# EASYEADA_SCH_WaterLevelAtmega328_2022-11.net
KiCad netlist of a schematic drawn in EasyEDA
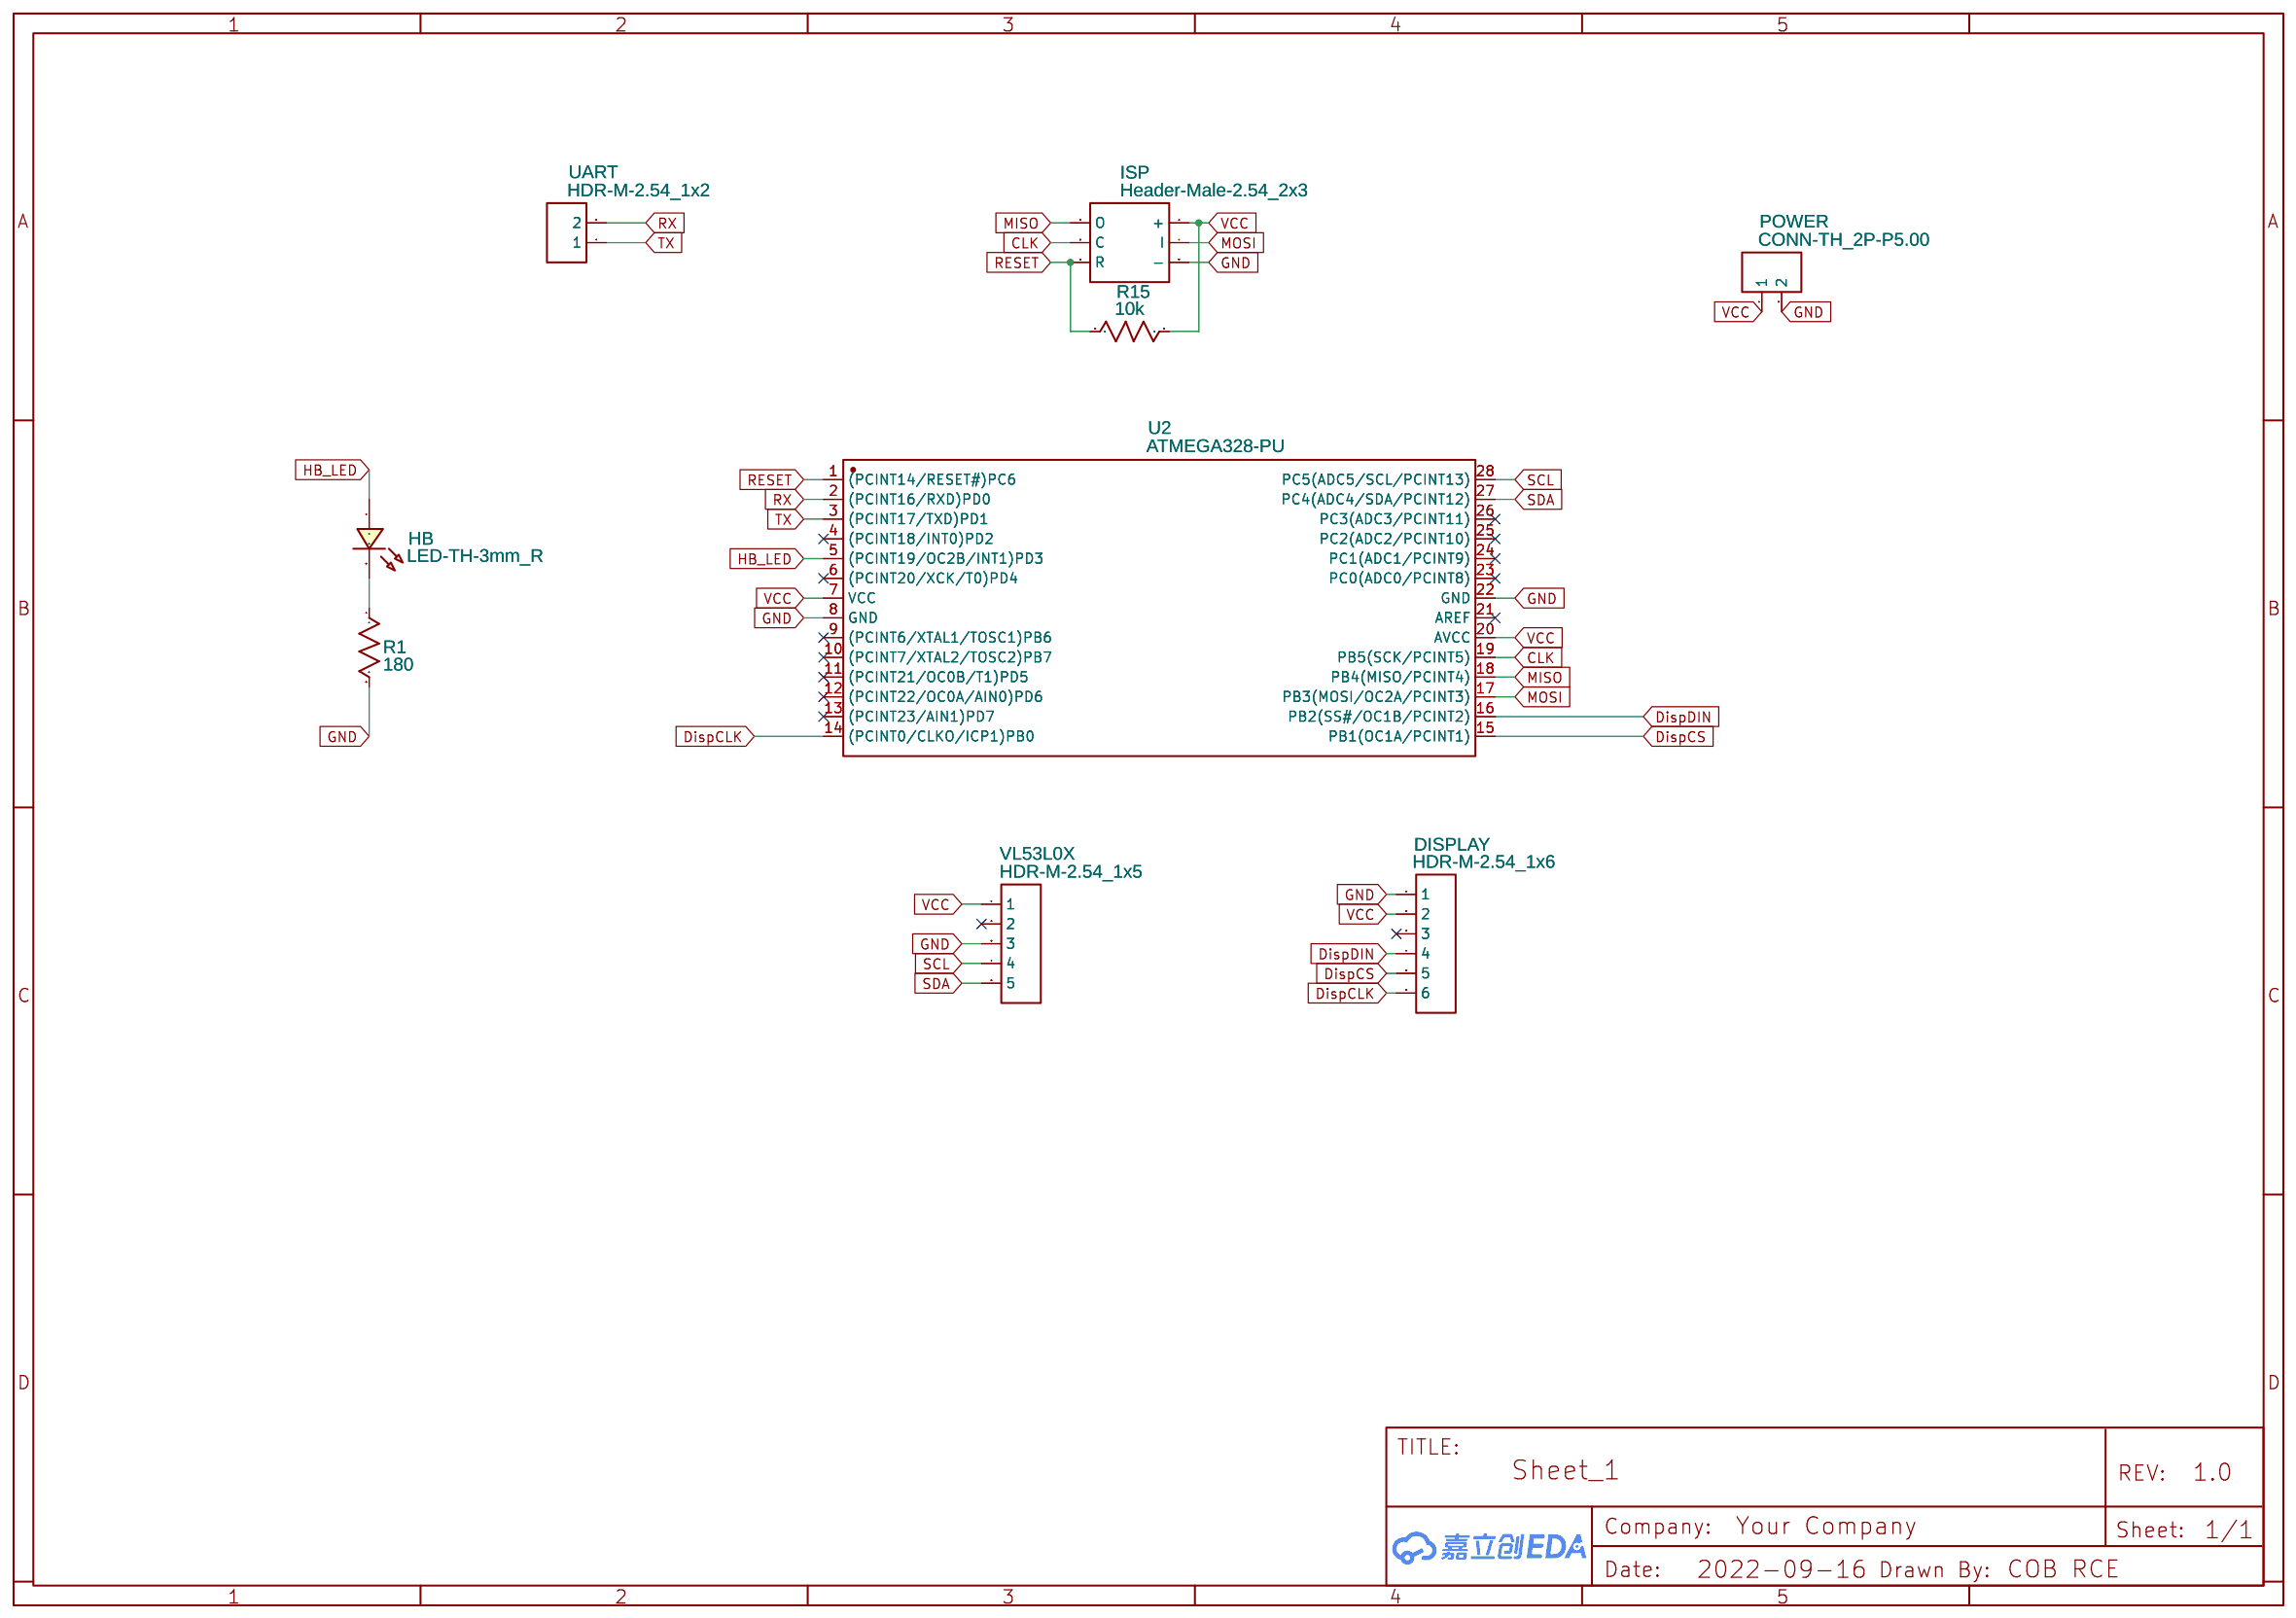
[diagram p0: schematic sheet]

(export (version "E")
  (design (tool "Eeschema 10.0.6"))
  (components
    (comp (ref "DISPLAY")
      (value "HDR-M-2.54_1x6")
      (fields (field (name "BOM_Supplier Part") "C190819"))
      (libsource (lib "") (part "HDR-M-2.54_1x6"))
    )
    (comp (ref "HB")
      (value "LED-TH-3mm_R")
      (fields
        (field (name "BOM_Manufacturer Part") "204-10SDRD/S530-A3-L")
        (field (name "BOM_Supplier Part") "C84774")
      )
      (libsource (lib "") (part "LED-TH-3mm_R"))
    )
    (comp (ref "ISP")
      (value "Header-Male-2.54_2x3")
      (fields (field (name "BOM_Supplier Part") "C65114"))
      (libsource (lib "") (part "Unknown_565_-690"))
    )
    (comp (ref "POWER") (value "CONN-TH_2P-P5.00") (libsource (lib "") (part "CONN-TH_2P-P5.00")))
    (comp (ref "R1")
      (value "180")
      (fields (field (name "BOM_Manufacturer Part") "?"))
      (libsource (lib "") (part "Res_AXIAL-0.3(1/8W)_US_1"))
    )
    (comp (ref "R15")
      (value "10k")
      (fields (field (name "BOM_Manufacturer Part") "?"))
      (libsource (lib "") (part "Res_AXIAL-0.3(1/8W)_US"))
    )
    (comp (ref "U2")
      (value "ATMEGA328-PU")
      (fields (field (name "BOM_Supplier Part") "C613508"))
      (libsource (lib "") (part "ATMEGA328-PU"))
    )
    (comp (ref "UART")
      (value "HDR-M-2.54_1x2")
      (fields (field (name "BOM_Supplier Part") "C124375"))
      (libsource (lib "") (part "HDR-M-2.54_1x2"))
    )
    (comp (ref "VL53L0X")
      (value "HDR-M-2.54_1x5")
      (fields (field (name "BOM_Supplier Part") "C358687"))
      (libsource (lib "") (part "HDR-M-2.54_1x5"))
    )
  )
  (nets
    (net (code "1") (name "CLK") (class "Default")
      (node (ref "ISP") (pin "3") (pinfunction "C_3") (pintype "input"))
      (node (ref "U2") (pin "19") (pinfunction "PB5(SCK/PCINT5)_19") (pintype "unspecified"))
    )
    (net (code "2") (name "DispCLK") (class "Default")
      (node (ref "DISPLAY") (pin "6") (pinfunction "6_6") (pintype "input"))
      (node (ref "U2") (pin "14") (pinfunction "(PCINT0/CLKO/ICP1)PB0_14") (pintype "unspecified"))
    )
    (net (code "3") (name "DispCS") (class "Default")
      (node (ref "DISPLAY") (pin "5") (pinfunction "5_5") (pintype "input"))
      (node (ref "U2") (pin "15") (pinfunction "PB1(OC1A/PCINT1)_15") (pintype "unspecified"))
    )
    (net (code "4") (name "DispDIN") (class "Default")
      (node (ref "DISPLAY") (pin "4") (pinfunction "4_4") (pintype "input"))
      (node (ref "U2") (pin "16") (pinfunction "PB2(SS#/OC1B/PCINT2)_16") (pintype "unspecified"))
    )
    (net (code "5") (name "GND") (class "Default")
      (node (ref "DISPLAY") (pin "1") (pinfunction "1_1") (pintype "input"))
      (node (ref "ISP") (pin "6") (pinfunction "-_6") (pintype "input"))
      (node (ref "POWER") (pin "2") (pinfunction "2_2") (pintype "unspecified"))
      (node (ref "R1") (pin "2") (pinfunction "2_2") (pintype "unspecified"))
      (node (ref "U2") (pin "22") (pinfunction "GND_22") (pintype "unspecified"))
      (node (ref "U2") (pin "8") (pinfunction "GND_8") (pintype "unspecified"))
      (node (ref "VL53L0X") (pin "3") (pinfunction "3_3") (pintype "unspecified"))
    )
    (net (code "6") (name "HB_LED") (class "Default")
      (node (ref "HB") (pin "1") (pinfunction "1_1") (pintype "unspecified"))
      (node (ref "U2") (pin "5") (pinfunction "(PCINT19/OC2B/INT1)PD3_5") (pintype "unspecified"))
    )
    (net (code "7") (name "MISO") (class "Default")
      (node (ref "ISP") (pin "1") (pinfunction "O_1") (pintype "input"))
      (node (ref "U2") (pin "18") (pinfunction "PB4(MISO/PCINT4)_18") (pintype "unspecified"))
    )
    (net (code "8") (name "MOSI") (class "Default")
      (node (ref "ISP") (pin "4") (pinfunction "I_4") (pintype "input"))
      (node (ref "U2") (pin "17") (pinfunction "PB3(MOSI/OC2A/PCINT3)_17") (pintype "unspecified"))
    )
    (net (code "9") (name "Net-(HB-Pad2)") (class "Default")
      (node (ref "HB") (pin "2") (pinfunction "2_2") (pintype "unspecified"))
      (node (ref "R1") (pin "1") (pinfunction "1_1") (pintype "unspecified"))
    )
    (net (code "10") (name "RESET") (class "Default")
      (node (ref "ISP") (pin "5") (pinfunction "R_5") (pintype "input"))
      (node (ref "R15") (pin "1") (pinfunction "1_1") (pintype "unspecified"))
      (node (ref "U2") (pin "1") (pinfunction "(PCINT14/RESET#)PC6_1") (pintype "unspecified"))
    )
    (net (code "11") (name "RX") (class "Default")
      (node (ref "U2") (pin "2") (pinfunction "(PCINT16/RXD)PD0_2") (pintype "unspecified"))
      (node (ref "UART") (pin "2") (pinfunction "2_2") (pintype "unspecified"))
    )
    (net (code "12") (name "SCL") (class "Default")
      (node (ref "U2") (pin "28") (pinfunction "PC5(ADC5/SCL/PCINT13)_28") (pintype "unspecified"))
      (node (ref "VL53L0X") (pin "4") (pinfunction "4_4") (pintype "unspecified"))
    )
    (net (code "13") (name "SDA") (class "Default")
      (node (ref "U2") (pin "27") (pinfunction "PC4(ADC4/SDA/PCINT12)_27") (pintype "unspecified"))
      (node (ref "VL53L0X") (pin "5") (pinfunction "5_5") (pintype "unspecified"))
    )
    (net (code "14") (name "TX") (class "Default")
      (node (ref "U2") (pin "3") (pinfunction "(PCINT17/TXD)PD1_3") (pintype "unspecified"))
      (node (ref "UART") (pin "1") (pinfunction "1_1") (pintype "unspecified"))
    )
    (net (code "15") (name "VCC") (class "Default")
      (node (ref "DISPLAY") (pin "2") (pinfunction "2_2") (pintype "input"))
      (node (ref "ISP") (pin "2") (pinfunction "+_2") (pintype "input"))
      (node (ref "POWER") (pin "1") (pinfunction "1_1") (pintype "unspecified"))
      (node (ref "R15") (pin "2") (pinfunction "2_2") (pintype "unspecified"))
      (node (ref "U2") (pin "20") (pinfunction "AVCC_20") (pintype "unspecified"))
      (node (ref "U2") (pin "7") (pinfunction "VCC_7") (pintype "unspecified"))
      (node (ref "VL53L0X") (pin "1") (pinfunction "1_1") (pintype "unspecified"))
    )
    (net (code "16") (name "unconnected-(DISPLAY-Pad3)") (class "Default")
      (node (ref "DISPLAY") (pin "3") (pinfunction "3_3") (pintype "input+no_connect"))
    )
    (net (code "17") (name "unconnected-(U2-(PCINT6{slash}XTAL1{slash}TOSC1)PB6-Pad9)") (class "Default")
      (node (ref "U2") (pin "9") (pinfunction "(PCINT6/XTAL1/TOSC1)PB6_9") (pintype "unspecified+no_connect"))
    )
    (net (code "18") (name "unconnected-(U2-(PCINT7{slash}XTAL2{slash}TOSC2)PB7-Pad10)") (class "Default")
      (node (ref "U2") (pin "10") (pinfunction "(PCINT7/XTAL2/TOSC2)PB7_10") (pintype "unspecified+no_connect"))
    )
    (net (code "19") (name "unconnected-(U2-(PCINT18{slash}INT0)PD2-Pad4)") (class "Default")
      (node (ref "U2") (pin "4") (pinfunction "(PCINT18/INT0)PD2_4") (pintype "unspecified+no_connect"))
    )
    (net (code "20") (name "unconnected-(U2-(PCINT20{slash}XCK{slash}T0)PD4-Pad6)") (class "Default")
      (node (ref "U2") (pin "6") (pinfunction "(PCINT20/XCK/T0)PD4_6") (pintype "unspecified+no_connect"))
    )
    (net (code "21") (name "unconnected-(U2-(PCINT21{slash}OC0B{slash}T1)PD5-Pad11)") (class "Default")
      (node (ref "U2") (pin "11") (pinfunction "(PCINT21/OC0B/T1)PD5_11") (pintype "unspecified+no_connect"))
    )
    (net (code "22") (name "unconnected-(U2-(PCINT22{slash}OC0A{slash}AIN0)PD6-Pad12)") (class "Default")
      (node (ref "U2") (pin "12") (pinfunction "(PCINT22/OC0A/AIN0)PD6_12") (pintype "unspecified+no_connect"))
    )
    (net (code "23") (name "unconnected-(U2-(PCINT23{slash}AIN1)PD7-Pad13)") (class "Default")
      (node (ref "U2") (pin "13") (pinfunction "(PCINT23/AIN1)PD7_13") (pintype "unspecified+no_connect"))
    )
    (net (code "24") (name "unconnected-(U2-AREF-Pad21)") (class "Default")
      (node (ref "U2") (pin "21") (pinfunction "AREF_21") (pintype "unspecified+no_connect"))
    )
    (net (code "25") (name "unconnected-(U2-PC0(ADC0{slash}PCINT8)-Pad23)") (class "Default")
      (node (ref "U2") (pin "23") (pinfunction "PC0(ADC0/PCINT8)_23") (pintype "unspecified+no_connect"))
    )
    (net (code "26") (name "unconnected-(U2-PC1(ADC1{slash}PCINT9)-Pad24)") (class "Default")
      (node (ref "U2") (pin "24") (pinfunction "PC1(ADC1/PCINT9)_24") (pintype "unspecified+no_connect"))
    )
    (net (code "27") (name "unconnected-(U2-PC2(ADC2{slash}PCINT10)-Pad25)") (class "Default")
      (node (ref "U2") (pin "25") (pinfunction "PC2(ADC2/PCINT10)_25") (pintype "unspecified+no_connect"))
    )
    (net (code "28") (name "unconnected-(U2-PC3(ADC3{slash}PCINT11)-Pad26)") (class "Default")
      (node (ref "U2") (pin "26") (pinfunction "PC3(ADC3/PCINT11)_26") (pintype "unspecified+no_connect"))
    )
    (net (code "29") (name "unconnected-(VL53L0X-Pad2)") (class "Default")
      (node (ref "VL53L0X") (pin "2") (pinfunction "2_2") (pintype "unspecified+no_connect"))
    )
  )
)
